# 10_CAN.net
KiCad netlist of a schematic drawn in Altium Designer
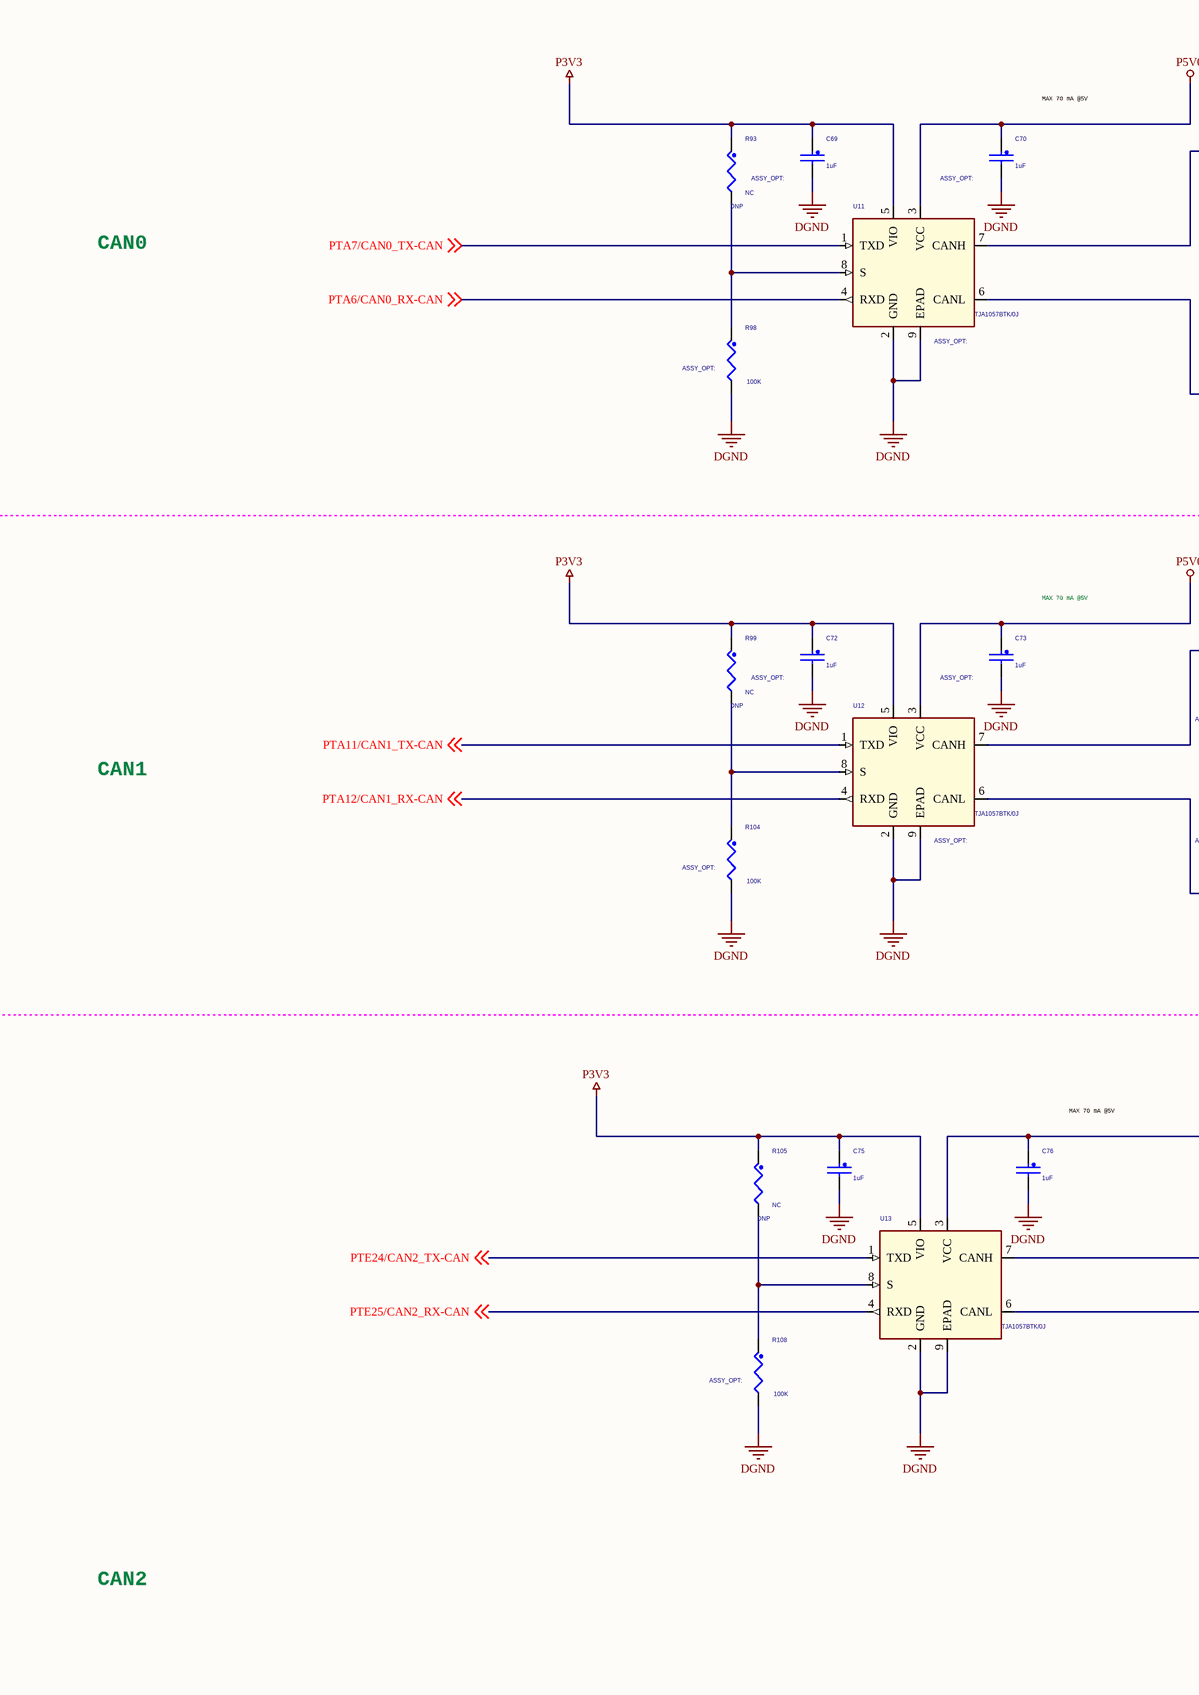
[diagram p0: 10 CAN.SchDoc, left]
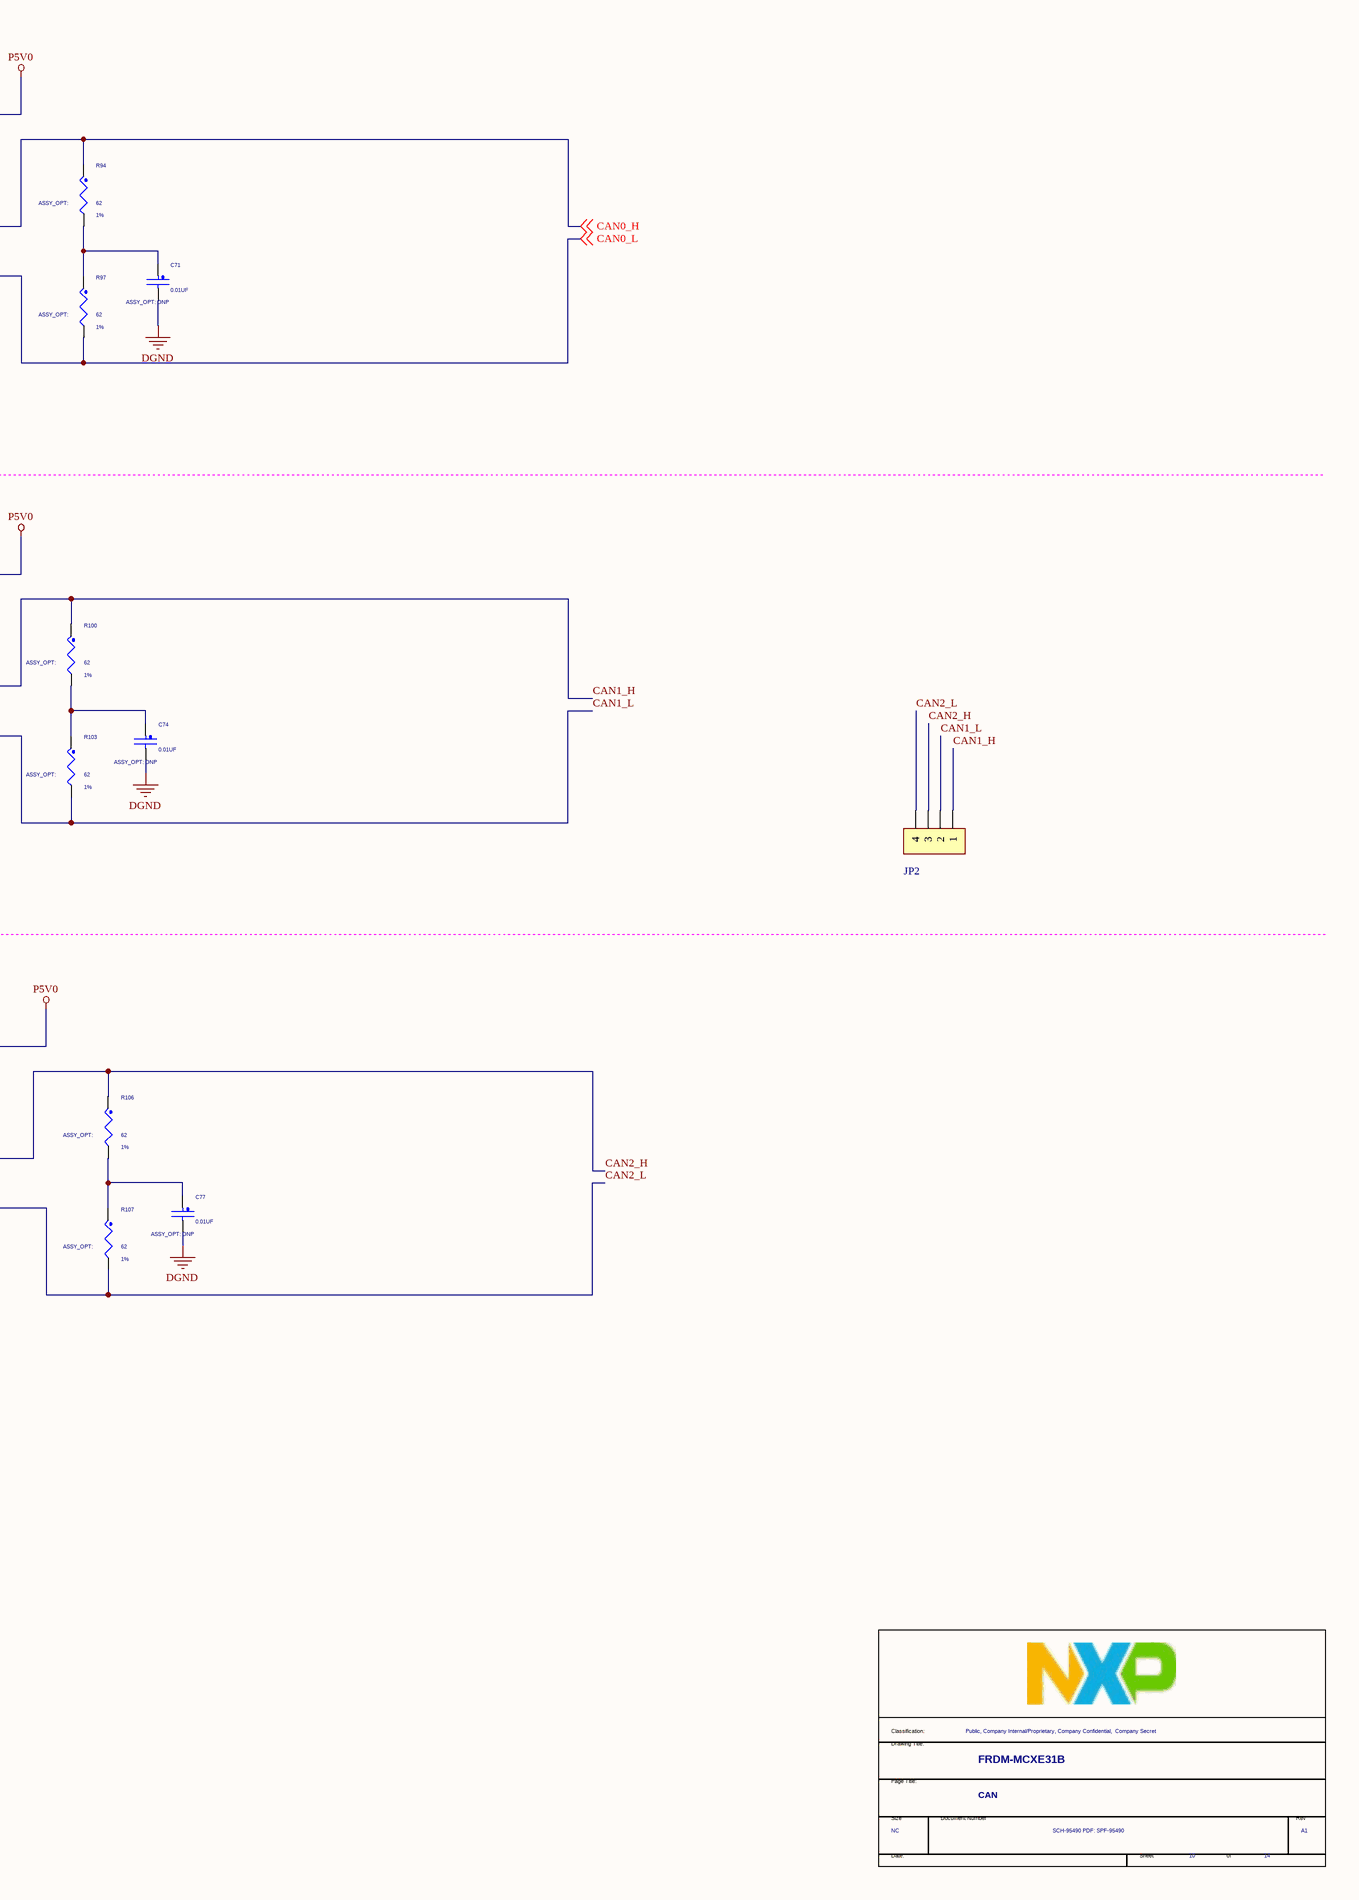
[diagram p1: 10 CAN.SchDoc, right]

(export (version "E")
  (design (tool "Eeschema 10.0.6"))
  (components
    (comp (ref "C69")
      (value "1uF")
      (footprint "CC0402_25")
      (description "CAP CER 1.0uF 16V 10% X6S 0402")
      (fields (field (name "VOLTAGE") "16V") (field (name "TOLERANCE") "10%"))
      (libsource (lib "*") (part "CAP_NP"))
    )
    (comp (ref "C70")
      (value "1uF")
      (footprint "CC0402_25")
      (description "CAP CER 1.0uF 16V 10% X6S 0402")
      (fields (field (name "VOLTAGE") "16V") (field (name "TOLERANCE") "10%"))
      (libsource (lib "*") (part "CAP_NP"))
    )
    (comp (ref "C71")
      (value "0.01UF")
      (footprint "CC0402_25")
      (description "CAP CER 0.01UF 50V 10% X7R 0402")
      (fields (field (name "ASSY_OPT") "DNP") (field (name "TOLERANCE") "10%"))
      (libsource (lib "*") (part "CAP_NP"))
    )
    (comp (ref "C72")
      (value "1uF")
      (footprint "CC0402_25")
      (description "CAP CER 1.0uF 16V 10% X6S 0402")
      (fields (field (name "TOLERANCE") "10%") (field (name "VOLTAGE") "16V"))
      (libsource (lib "*") (part "CAP_NP"))
    )
    (comp (ref "C73")
      (value "1uF")
      (footprint "CC0402_25")
      (description "CAP CER 1.0uF 16V 10% X6S 0402")
      (fields (field (name "TOLERANCE") "10%") (field (name "VOLTAGE") "16V"))
      (libsource (lib "*") (part "CAP_NP"))
    )
    (comp (ref "C74")
      (value "0.01UF")
      (footprint "CC0402_25")
      (description "CAP CER 0.01UF 50V 10% X7R 0402")
      (fields (field (name "ASSY_OPT") "DNP") (field (name "TOLERANCE") "10%"))
      (libsource (lib "*") (part "CAP_NP"))
    )
    (comp (ref "C75")
      (value "1uF")
      (footprint "CC0402_25")
      (description "CAP CER 1.0uF 16V 10% X6S 0402")
      (fields (field (name "VOLTAGE") "16V") (field (name "TOLERANCE") "10%"))
      (libsource (lib "*") (part "CAP_NP"))
    )
    (comp (ref "C76")
      (value "1uF")
      (footprint "CC0402_25")
      (description "CAP CER 1.0uF 16V 10% X6S 0402")
      (fields (field (name "TOLERANCE") "10%") (field (name "VOLTAGE") "16V"))
      (libsource (lib "*") (part "CAP_NP"))
    )
    (comp (ref "C77")
      (value "0.01UF")
      (footprint "CC0402_25")
      (description "CAP CER 0.01UF 50V 10% X7R 0402")
      (fields (field (name "ASSY_OPT") "DNP") (field (name "TOLERANCE") "10%"))
      (libsource (lib "*") (part "CAP_NP"))
    )
    (comp (ref "JP2")
      (value "HDR-1X4")
      (footprint "KF128-3.81-4P")
      (description "4P接插件")
      (libsource (lib "4.8   - 接插件-脚距3.81") (part "Header 4"))
    )
    (comp (ref "R93")
      (value "NC")
      (footprint "RC0402_25")
      (description "RES MF 10K 1/16W 5% 0402")
      (fields (field (name "ASSY_OPT") "DNP") (field (name "TOLERANCE") "5%"))
      (libsource (lib "*") (part "RES"))
    )
    (comp (ref "R94")
      (value "62")
      (footprint "RC0805_OV")
      (description "RES MF 62 OHM 1/4W 1% AEC-Q200 0805")
      (fields (field (name "TOLERANCE") "1%"))
      (libsource (lib "*") (part "RES"))
    )
    (comp (ref "R97")
      (value "62")
      (footprint "RC0805_OV")
      (description "RES MF 62 OHM 1/4W 1% AEC-Q200 0805")
      (fields (field (name "TOLERANCE") "1%"))
      (libsource (lib "*") (part "RES"))
    )
    (comp (ref "R98")
      (value "100K")
      (footprint "RC0402_25")
      (description "RES MF 100K 1/16W 1% 0402")
      (fields (field (name "TOLERANCE") "1%"))
      (libsource (lib "*") (part "RES"))
    )
    (comp (ref "R99")
      (value "NC")
      (footprint "RC0402_25")
      (description "RES MF 10K 1/16W 5% 0402")
      (fields (field (name "ASSY_OPT") "DNP") (field (name "TOLERANCE") "5%"))
      (libsource (lib "*") (part "RES"))
    )
    (comp (ref "R100")
      (value "62")
      (footprint "RC0805_OV")
      (description "RES MF 62 OHM 1/4W 1% AEC-Q200 0805")
      (fields (field (name "TOLERANCE") "1%"))
      (libsource (lib "*") (part "RES"))
    )
    (comp (ref "R103")
      (value "62")
      (footprint "RC0805_OV")
      (description "RES MF 62 OHM 1/4W 1% AEC-Q200 0805")
      (fields (field (name "TOLERANCE") "1%"))
      (libsource (lib "*") (part "RES"))
    )
    (comp (ref "R104")
      (value "100K")
      (footprint "RC0402_25")
      (description "RES MF 100K 1/16W 1% 0402")
      (fields (field (name "TOLERANCE") "1%"))
      (libsource (lib "*") (part "RES"))
    )
    (comp (ref "R105")
      (value "NC")
      (footprint "RC0402_25")
      (description "RES MF 10K 1/16W 5% 0402")
      (fields (field (name "ASSY_OPT") "DNP") (field (name "TOLERANCE") "5%"))
      (libsource (lib "*") (part "RES"))
    )
    (comp (ref "R106")
      (value "62")
      (footprint "RC0805_OV")
      (description "RES MF 62 OHM 1/4W 1% AEC-Q200 0805")
      (fields (field (name "TOLERANCE") "1%"))
      (libsource (lib "*") (part "RES"))
    )
    (comp (ref "R107")
      (value "62")
      (footprint "RC0805_OV")
      (description "RES MF 62 OHM 1/4W 1% AEC-Q200 0805")
      (fields (field (name "TOLERANCE") "1%"))
      (libsource (lib "*") (part "RES"))
    )
    (comp (ref "R108")
      (value "100K")
      (footprint "RC0402_25")
      (description "RES MF 100K 1/16W 1% 0402")
      (fields (field (name "TOLERANCE") "1%"))
      (libsource (lib "*") (part "RES"))
    )
    (comp (ref "U11")
      (value "TJA1057BTK")
      (footprint "son8_0p65_3p15x3p15")
      (description "IC XCVR CAN 4.5-5.5V AEC-Q100 HVSON8")
      (fields (field (name "MFG_PN01") "TJA1057BTK/0J"))
      (libsource (lib "*") (part "TJA1051TK_3_HVSON8"))
    )
    (comp (ref "U12")
      (value "TJA1057BTK")
      (footprint "son8_0p65_3p15x3p15")
      (description "IC XCVR CAN 4.5-5.5V AEC-Q100 HVSON8")
      (fields (field (name "MFG_PN01") "TJA1057BTK/0J"))
      (libsource (lib "*") (part "TJA1051TK_3_HVSON8"))
    )
    (comp (ref "U13")
      (value "TJA1057BTK")
      (footprint "son8_0p65_3p15x3p15")
      (description "IC XCVR CAN 4.5-5.5V AEC-Q100 HVSON8")
      (fields (field (name "MFG_PN01") "TJA1057BTK/0J"))
      (libsource (lib "*") (part "TJA1051TK_3_HVSON8"))
    )
  )
  (nets
    (net (code "1") (name "/CAN1_H") (class "Default")
      (node (ref "JP2") (pin "1") (pinfunction "1_1") (pintype "passive"))
      (node (ref "R100") (pin "1") (pinfunction "1_1") (pintype "passive"))
      (node (ref "U12") (pin "7") (pinfunction "CANH_7") (pintype "bidirectional"))
    )
    (net (code "2") (name "/CAN1_L") (class "Default")
      (node (ref "JP2") (pin "2") (pinfunction "2_2") (pintype "passive"))
      (node (ref "R103") (pin "2") (pinfunction "2_2") (pintype "passive"))
      (node (ref "U12") (pin "6") (pinfunction "CANL_6") (pintype "bidirectional"))
    )
    (net (code "3") (name "/CAN2_H") (class "Default")
      (node (ref "JP2") (pin "3") (pinfunction "3_3") (pintype "passive"))
      (node (ref "R106") (pin "1") (pinfunction "1_1") (pintype "passive"))
      (node (ref "U13") (pin "7") (pinfunction "CANH_7") (pintype "bidirectional"))
    )
    (net (code "4") (name "/CAN2_L") (class "Default")
      (node (ref "JP2") (pin "4") (pinfunction "4_4") (pintype "passive"))
      (node (ref "R107") (pin "2") (pinfunction "2_2") (pintype "passive"))
      (node (ref "U13") (pin "6") (pinfunction "CANL_6") (pintype "bidirectional"))
    )
    (net (code "5") (name "CAN0_H") (class "Default")
      (node (ref "R94") (pin "1") (pinfunction "1_1") (pintype "passive"))
      (node (ref "U11") (pin "7") (pinfunction "CANH_7") (pintype "bidirectional"))
    )
    (net (code "6") (name "CAN0_L") (class "Default")
      (node (ref "R97") (pin "2") (pinfunction "2_2") (pintype "passive"))
      (node (ref "U11") (pin "6") (pinfunction "CANL_6") (pintype "bidirectional"))
    )
    (net (code "7") (name "DGND") (class "Default")
      (node (ref "C69") (pin "2") (pinfunction "2_2") (pintype "passive"))
      (node (ref "C70") (pin "2") (pinfunction "2_2") (pintype "passive"))
      (node (ref "C71") (pin "2") (pinfunction "2_2") (pintype "passive"))
      (node (ref "C72") (pin "2") (pinfunction "2_2") (pintype "passive"))
      (node (ref "C73") (pin "2") (pinfunction "2_2") (pintype "passive"))
      (node (ref "C74") (pin "2") (pinfunction "2_2") (pintype "passive"))
      (node (ref "C75") (pin "2") (pinfunction "2_2") (pintype "passive"))
      (node (ref "C76") (pin "2") (pinfunction "2_2") (pintype "passive"))
      (node (ref "C77") (pin "2") (pinfunction "2_2") (pintype "passive"))
      (node (ref "R104") (pin "2") (pinfunction "2_2") (pintype "passive"))
      (node (ref "R108") (pin "2") (pinfunction "2_2") (pintype "passive"))
      (node (ref "R98") (pin "2") (pinfunction "2_2") (pintype "passive"))
      (node (ref "U11") (pin "2") (pinfunction "GND_2") (pintype "power_in"))
      (node (ref "U11") (pin "9") (pinfunction "EPAD_9") (pintype "power_in"))
      (node (ref "U12") (pin "2") (pinfunction "GND_2") (pintype "power_in"))
      (node (ref "U12") (pin "9") (pinfunction "EPAD_9") (pintype "power_in"))
      (node (ref "U13") (pin "2") (pinfunction "GND_2") (pintype "power_in"))
      (node (ref "U13") (pin "9") (pinfunction "EPAD_9") (pintype "power_in"))
    )
    (net (code "8") (name "Net-(C71-Pad1)") (class "Default")
      (node (ref "C71") (pin "1") (pinfunction "1_1") (pintype "passive"))
      (node (ref "R94") (pin "2") (pinfunction "2_2") (pintype "passive"))
      (node (ref "R97") (pin "1") (pinfunction "1_1") (pintype "passive"))
    )
    (net (code "9") (name "Net-(C74-Pad1)") (class "Default")
      (node (ref "C74") (pin "1") (pinfunction "1_1") (pintype "passive"))
      (node (ref "R100") (pin "2") (pinfunction "2_2") (pintype "passive"))
      (node (ref "R103") (pin "1") (pinfunction "1_1") (pintype "passive"))
    )
    (net (code "10") (name "Net-(C77-Pad1)") (class "Default")
      (node (ref "C77") (pin "1") (pinfunction "1_1") (pintype "passive"))
      (node (ref "R106") (pin "2") (pinfunction "2_2") (pintype "passive"))
      (node (ref "R107") (pin "1") (pinfunction "1_1") (pintype "passive"))
    )
    (net (code "11") (name "Net-(U11-S)") (class "Default")
      (node (ref "R93") (pin "2") (pinfunction "2_2") (pintype "passive"))
      (node (ref "R98") (pin "1") (pinfunction "1_1") (pintype "passive"))
      (node (ref "U11") (pin "8") (pinfunction "S_8") (pintype "input"))
    )
    (net (code "12") (name "Net-(U12-S)") (class "Default")
      (node (ref "R104") (pin "1") (pinfunction "1_1") (pintype "passive"))
      (node (ref "R99") (pin "2") (pinfunction "2_2") (pintype "passive"))
      (node (ref "U12") (pin "8") (pinfunction "S_8") (pintype "input"))
    )
    (net (code "13") (name "Net-(U13-S)") (class "Default")
      (node (ref "R105") (pin "2") (pinfunction "2_2") (pintype "passive"))
      (node (ref "R108") (pin "1") (pinfunction "1_1") (pintype "passive"))
      (node (ref "U13") (pin "8") (pinfunction "S_8") (pintype "input"))
    )
    (net (code "14") (name "P3V3") (class "Default")
      (node (ref "C69") (pin "1") (pinfunction "1_1") (pintype "passive"))
      (node (ref "C72") (pin "1") (pinfunction "1_1") (pintype "passive"))
      (node (ref "C75") (pin "1") (pinfunction "1_1") (pintype "passive"))
      (node (ref "R105") (pin "1") (pinfunction "1_1") (pintype "passive"))
      (node (ref "R93") (pin "1") (pinfunction "1_1") (pintype "passive"))
      (node (ref "R99") (pin "1") (pinfunction "1_1") (pintype "passive"))
      (node (ref "U11") (pin "5") (pinfunction "VIO_5") (pintype "power_in"))
      (node (ref "U12") (pin "5") (pinfunction "VIO_5") (pintype "power_in"))
      (node (ref "U13") (pin "5") (pinfunction "VIO_5") (pintype "power_in"))
    )
    (net (code "15") (name "P5V0") (class "Default")
      (node (ref "C70") (pin "1") (pinfunction "1_1") (pintype "passive"))
      (node (ref "C73") (pin "1") (pinfunction "1_1") (pintype "passive"))
      (node (ref "C76") (pin "1") (pinfunction "1_1") (pintype "passive"))
      (node (ref "U11") (pin "3") (pinfunction "VCC_3") (pintype "power_in"))
      (node (ref "U12") (pin "3") (pinfunction "VCC_3") (pintype "power_in"))
      (node (ref "U13") (pin "3") (pinfunction "VCC_3") (pintype "power_in"))
    )
    (net (code "16") (name "PTA6{slash}CAN0_RX-CAN") (class "Default")
      (node (ref "U11") (pin "4") (pinfunction "RXD_4") (pintype "output"))
    )
    (net (code "17") (name "PTA7{slash}CAN0_TX-CAN") (class "Default")
      (node (ref "U11") (pin "1") (pinfunction "TXD_1") (pintype "input"))
    )
    (net (code "18") (name "PTA11{slash}CAN1_TX-CAN") (class "Default")
      (node (ref "U12") (pin "1") (pinfunction "TXD_1") (pintype "input"))
    )
    (net (code "19") (name "PTA12{slash}CAN1_RX-CAN") (class "Default")
      (node (ref "U12") (pin "4") (pinfunction "RXD_4") (pintype "output"))
    )
    (net (code "20") (name "PTE24{slash}CAN2_TX-CAN") (class "Default")
      (node (ref "U13") (pin "1") (pinfunction "TXD_1") (pintype "input"))
    )
    (net (code "21") (name "PTE25{slash}CAN2_RX-CAN") (class "Default")
      (node (ref "U13") (pin "4") (pinfunction "RXD_4") (pintype "output"))
    )
  )
)
